# belamini-multi-a2.net
KiCad netlist of a schematic drawn in EAGLE
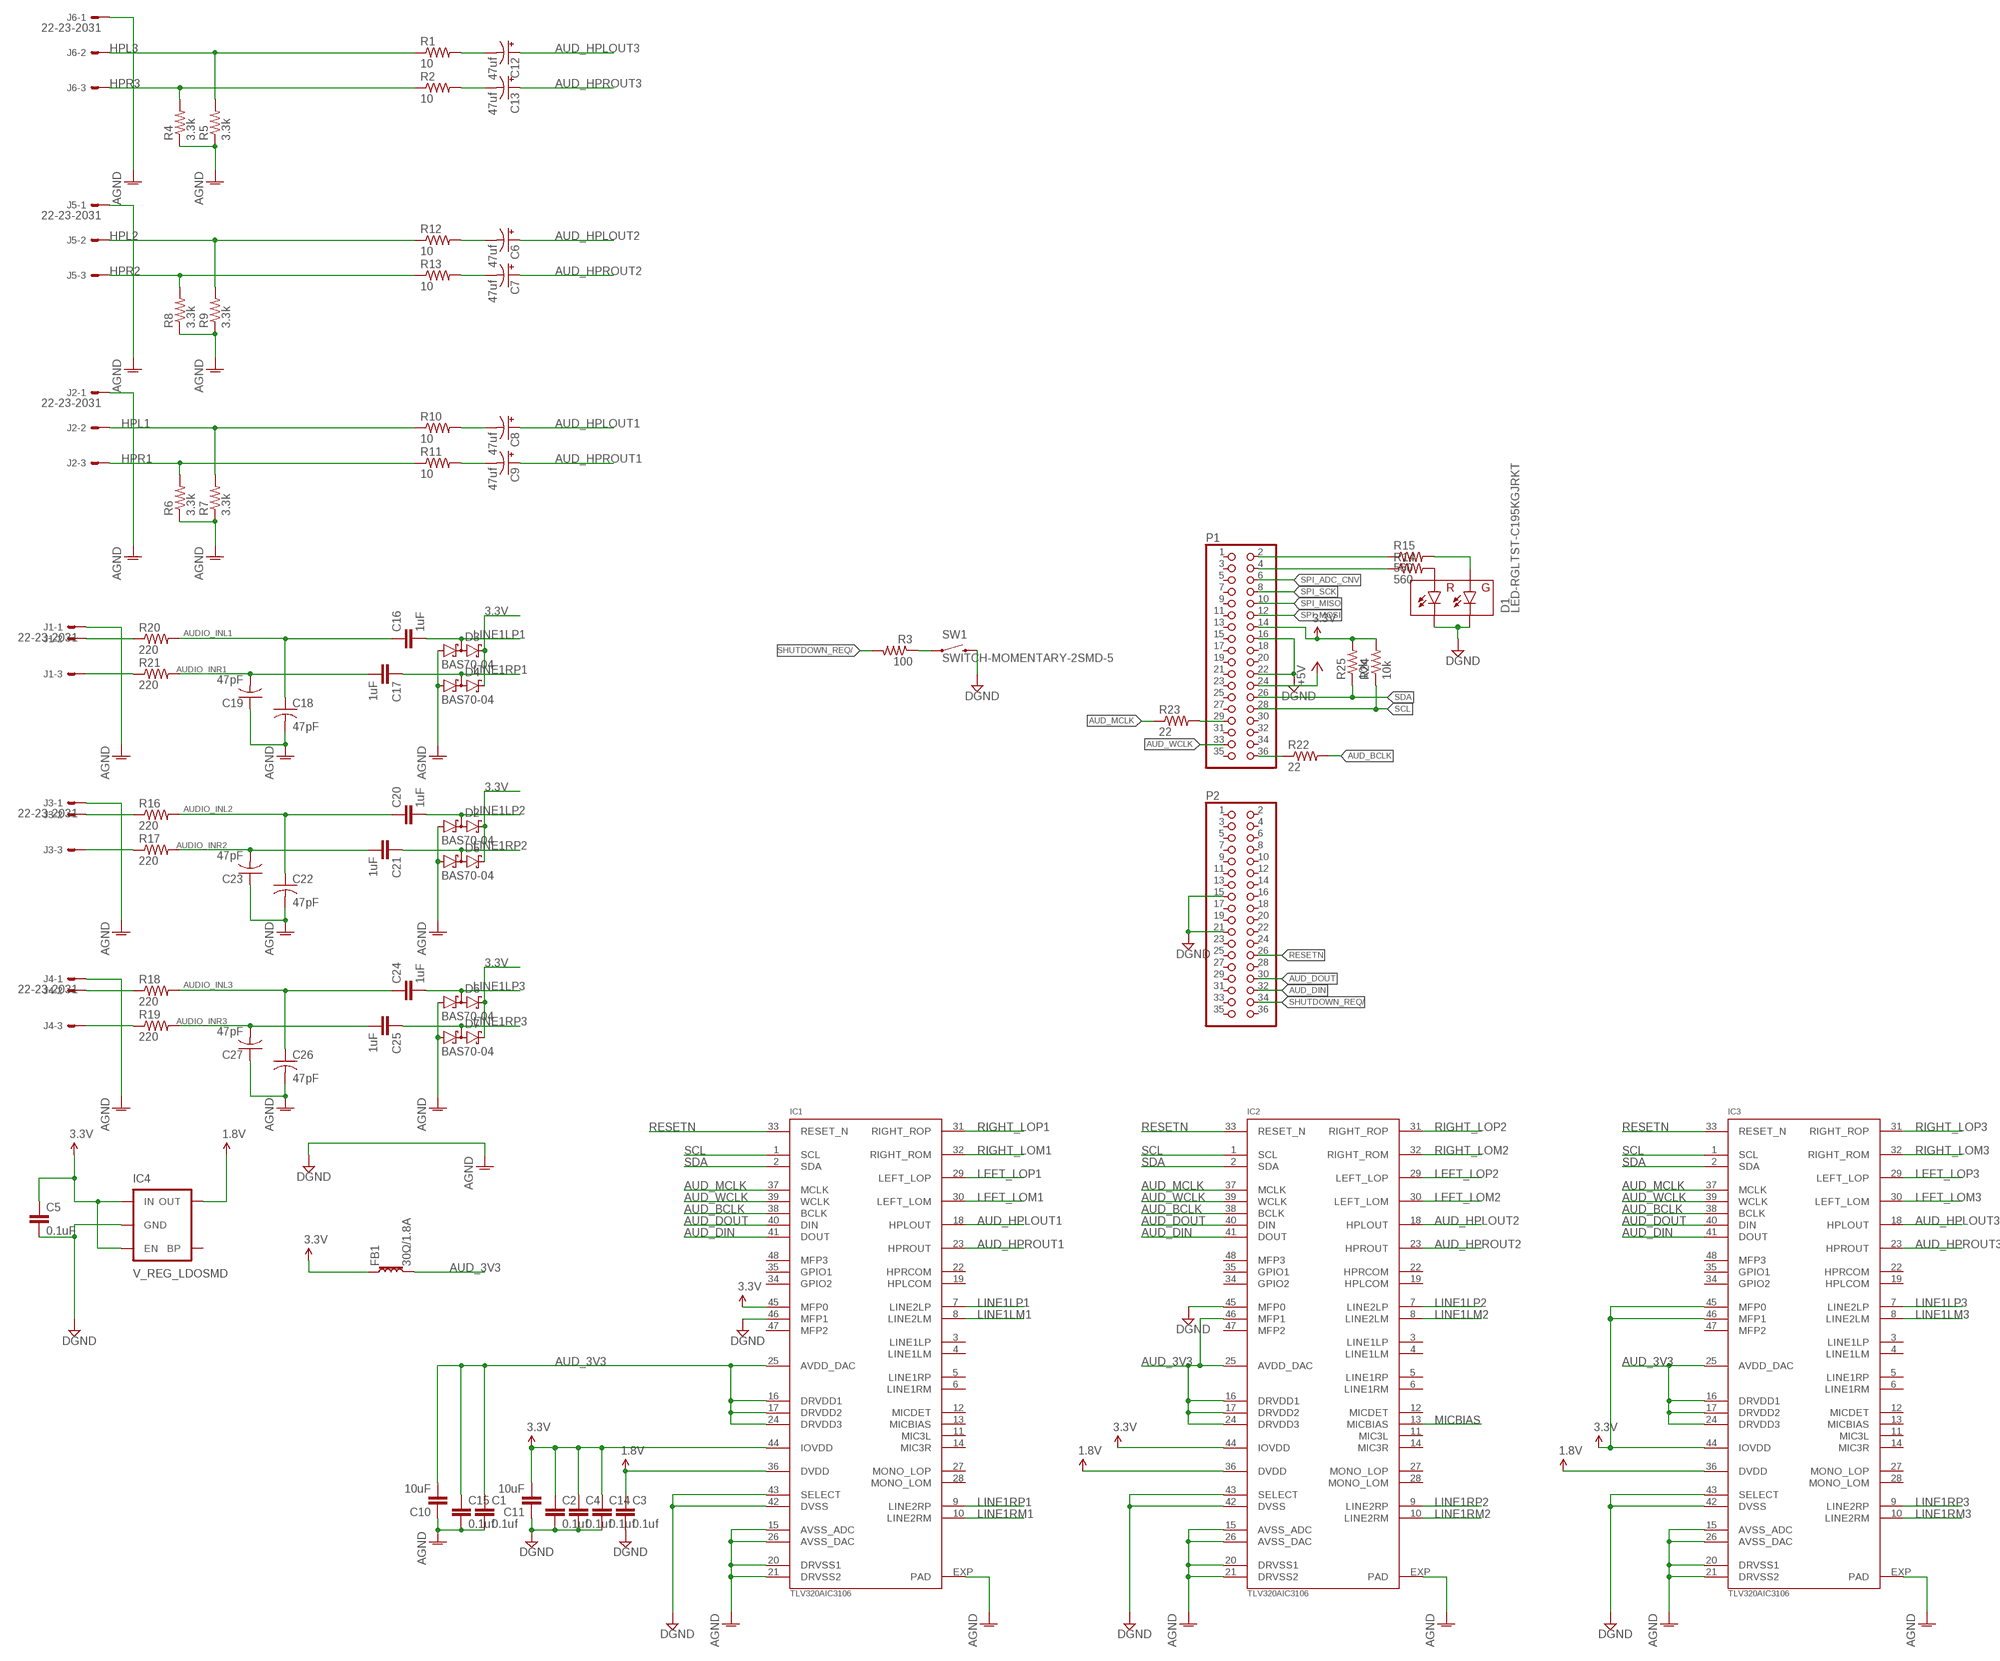
[diagram p0: schematic, sheet 1]

(export (version "E")
  (design (tool "Eeschema 10.0.6"))
  (components
    (comp (ref "C1")
      (value "0.1uf")
      (footprint "eagle-import:C0603")
      (libsource (lib "eagle-import") (part "C-EUC0603"))
    )
    (comp (ref "C2")
      (value "0.1uf")
      (footprint "eagle-import:C0603")
      (libsource (lib "eagle-import") (part "C-EUC0603"))
    )
    (comp (ref "C3")
      (value "0.1uf")
      (footprint "eagle-import:C0603")
      (libsource (lib "eagle-import") (part "C-EUC0603"))
    )
    (comp (ref "C4")
      (value "0.1uf")
      (footprint "eagle-import:C0603")
      (libsource (lib "eagle-import") (part "C-EUC0603"))
    )
    (comp (ref "C5")
      (value "0.1uF")
      (footprint "eagle-import:C0603")
      (libsource (lib "eagle-import") (part "C-EUC0603"))
    )
    (comp (ref "C6")
      (value "47uf")
      (footprint "eagle-import:EIA3216")
      (libsource (lib "eagle-import") (part "CAP_POL1206"))
    )
    (comp (ref "C7")
      (value "47uf")
      (footprint "eagle-import:EIA3216")
      (libsource (lib "eagle-import") (part "CAP_POL1206"))
    )
    (comp (ref "C8")
      (value "47uf")
      (footprint "eagle-import:EIA3216")
      (libsource (lib "eagle-import") (part "CAP_POL1206"))
    )
    (comp (ref "C9")
      (value "47uf")
      (footprint "eagle-import:EIA3216")
      (libsource (lib "eagle-import") (part "CAP_POL1206"))
    )
    (comp (ref "C10")
      (value "10uF")
      (footprint "eagle-import:0603-CAP")
      (libsource (lib "eagle-import") (part "CAP0603-CAP"))
    )
    (comp (ref "C11")
      (value "10uF")
      (footprint "eagle-import:0603-CAP")
      (libsource (lib "eagle-import") (part "CAP0603-CAP"))
    )
    (comp (ref "C12")
      (value "47uf")
      (footprint "eagle-import:EIA3216")
      (libsource (lib "eagle-import") (part "CAP_POL1206"))
    )
    (comp (ref "C13")
      (value "47uf")
      (footprint "eagle-import:EIA3216")
      (libsource (lib "eagle-import") (part "CAP_POL1206"))
    )
    (comp (ref "C14")
      (value "0.1uf")
      (footprint "eagle-import:C0603")
      (libsource (lib "eagle-import") (part "C-EUC0603"))
    )
    (comp (ref "C15")
      (value "0.1uf")
      (footprint "eagle-import:C0603")
      (libsource (lib "eagle-import") (part "C-EUC0603"))
    )
    (comp (ref "C16")
      (value "1uF")
      (footprint "eagle-import:C0603")
      (libsource (lib "eagle-import") (part "C-EUC0603"))
    )
    (comp (ref "C17")
      (value "1uF")
      (footprint "eagle-import:C0603")
      (libsource (lib "eagle-import") (part "C-EUC0603"))
    )
    (comp (ref "C18")
      (value "47pF")
      (footprint "eagle-import:C0402-SMALL")
      (libsource (lib "eagle-import") (part "C0402-SMALL"))
    )
    (comp (ref "C19")
      (value "47pF")
      (footprint "eagle-import:C0402-SMALL")
      (libsource (lib "eagle-import") (part "C0402-SMALL"))
    )
    (comp (ref "C20")
      (value "1uF")
      (footprint "eagle-import:C0603")
      (libsource (lib "eagle-import") (part "C-EUC0603"))
    )
    (comp (ref "C21")
      (value "1uF")
      (footprint "eagle-import:C0603")
      (libsource (lib "eagle-import") (part "C-EUC0603"))
    )
    (comp (ref "C22")
      (value "47pF")
      (footprint "eagle-import:C0402-SMALL")
      (libsource (lib "eagle-import") (part "C0402-SMALL"))
    )
    (comp (ref "C23")
      (value "47pF")
      (footprint "eagle-import:C0402-SMALL")
      (libsource (lib "eagle-import") (part "C0402-SMALL"))
    )
    (comp (ref "C24")
      (value "1uF")
      (footprint "eagle-import:C0603")
      (libsource (lib "eagle-import") (part "C-EUC0603"))
    )
    (comp (ref "C25")
      (value "1uF")
      (footprint "eagle-import:C0603")
      (libsource (lib "eagle-import") (part "C-EUC0603"))
    )
    (comp (ref "C26")
      (value "47pF")
      (footprint "eagle-import:C0402-SMALL")
      (libsource (lib "eagle-import") (part "C0402-SMALL"))
    )
    (comp (ref "C27")
      (value "47pF")
      (footprint "eagle-import:C0402-SMALL")
      (libsource (lib "eagle-import") (part "C0402-SMALL"))
    )
    (comp (ref "D1")
      (value "LED-RGLTST-C195KGJRKT")
      (footprint "eagle-import:LTST-C195KGJRKT")
      (libsource (lib "eagle-import") (part "LED-RGLTST-C195KGJRKT"))
    )
    (comp (ref "D2")
      (value "BAS70-04")
      (footprint "eagle-import:SOT23")
      (libsource (lib "eagle-import") (part "BAS70-04"))
    )
    (comp (ref "D3")
      (value "BAS70-04")
      (footprint "eagle-import:SOT23")
      (libsource (lib "eagle-import") (part "BAS70-04"))
    )
    (comp (ref "D4")
      (value "BAS70-04")
      (footprint "eagle-import:SOT23")
      (libsource (lib "eagle-import") (part "BAS70-04"))
    )
    (comp (ref "D5")
      (value "BAS70-04")
      (footprint "eagle-import:SOT23")
      (libsource (lib "eagle-import") (part "BAS70-04"))
    )
    (comp (ref "D6")
      (value "BAS70-04")
      (footprint "eagle-import:SOT23")
      (libsource (lib "eagle-import") (part "BAS70-04"))
    )
    (comp (ref "D7")
      (value "BAS70-04")
      (footprint "eagle-import:SOT23")
      (libsource (lib "eagle-import") (part "BAS70-04"))
    )
    (comp (ref "FB1")
      (value "30Ω/1.8A")
      (footprint "eagle-import:0603")
      (libsource (lib "eagle-import") (part "FERRITE_BEAD-0603"))
    )
    (comp (ref "IC1")
      (value "TLV320AIC3106")
      (footprint "eagle-import:QFN48")
      (libsource (lib "eagle-import") (part "TLV320AIC3106IRGZR{dblquote}"))
    )
    (comp (ref "IC2")
      (value "TLV320AIC3106")
      (footprint "eagle-import:QFN48")
      (libsource (lib "eagle-import") (part "TLV320AIC3106IRGZR{dblquote}"))
    )
    (comp (ref "IC3")
      (value "TLV320AIC3106")
      (footprint "eagle-import:QFN48")
      (libsource (lib "eagle-import") (part "TLV320AIC3106IRGZR{dblquote}"))
    )
    (comp (ref "IC4")
      (value "V_REG_LDOSMD")
      (footprint "eagle-import:SOT23-5")
      (libsource (lib "eagle-import") (part "V_REG_LDOSMD"))
    )
    (comp (ref "J1")
      (value "22-23-2031")
      (footprint "eagle-import:22-23-2031")
      (fields (field (name "MF") "MOLEX"))
      (libsource (lib "eagle-import") (part "22-23-2031"))
    )
    (comp (ref "J2")
      (value "22-23-2031")
      (footprint "eagle-import:22-23-2031")
      (fields (field (name "MF") "MOLEX"))
      (libsource (lib "eagle-import") (part "con-molex_165_22-23-2031"))
    )
    (comp (ref "J3")
      (value "22-23-2031")
      (footprint "eagle-import:22-23-2031")
      (fields (field (name "MF") "MOLEX"))
      (libsource (lib "eagle-import") (part "22-23-2031"))
    )
    (comp (ref "J4")
      (value "22-23-2031")
      (footprint "eagle-import:22-23-2031")
      (fields (field (name "MF") "MOLEX"))
      (libsource (lib "eagle-import") (part "22-23-2031"))
    )
    (comp (ref "J5")
      (value "22-23-2031")
      (footprint "eagle-import:22-23-2031")
      (fields (field (name "MF") "MOLEX"))
      (libsource (lib "eagle-import") (part "con-molex_165_22-23-2031"))
    )
    (comp (ref "J6")
      (value "22-23-2031")
      (footprint "eagle-import:22-23-2031")
      (fields (field (name "MF") "MOLEX"))
      (libsource (lib "eagle-import") (part "con-molex_165_22-23-2031"))
    )
    (comp (ref "P1")
      (value "PINHD-2X18")
      (footprint "eagle-import:2X18")
      (libsource (lib "eagle-import") (part "PINHD-2X18"))
    )
    (comp (ref "P2")
      (value "PINHD-2X18")
      (footprint "eagle-import:2X18")
      (libsource (lib "eagle-import") (part "PINHD-2X18"))
    )
    (comp (ref "R1")
      (value "10")
      (footprint "eagle-import:C0402-SMALL")
      (libsource (lib "eagle-import") (part "R0402-SMALL"))
    )
    (comp (ref "R2")
      (value "10")
      (footprint "eagle-import:C0402-SMALL")
      (libsource (lib "eagle-import") (part "R0402-SMALL"))
    )
    (comp (ref "R3")
      (value "100")
      (footprint "eagle-import:C0402-SMALL")
      (libsource (lib "eagle-import") (part "R0402-SMALL"))
    )
    (comp (ref "R4")
      (value "3.3k")
      (footprint "eagle-import:C0402-SMALL")
      (libsource (lib "eagle-import") (part "R0402-SMALL"))
    )
    (comp (ref "R5")
      (value "3.3k")
      (footprint "eagle-import:C0402-SMALL")
      (libsource (lib "eagle-import") (part "R0402-SMALL"))
    )
    (comp (ref "R6")
      (value "3.3k")
      (footprint "eagle-import:C0402-SMALL")
      (libsource (lib "eagle-import") (part "R0402-SMALL"))
    )
    (comp (ref "R7")
      (value "3.3k")
      (footprint "eagle-import:C0402-SMALL")
      (libsource (lib "eagle-import") (part "R0402-SMALL"))
    )
    (comp (ref "R8")
      (value "3.3k")
      (footprint "eagle-import:C0402-SMALL")
      (libsource (lib "eagle-import") (part "R0402-SMALL"))
    )
    (comp (ref "R9")
      (value "3.3k")
      (footprint "eagle-import:C0402-SMALL")
      (libsource (lib "eagle-import") (part "R0402-SMALL"))
    )
    (comp (ref "R10")
      (value "10")
      (footprint "eagle-import:C0402-SMALL")
      (libsource (lib "eagle-import") (part "R0402-SMALL"))
    )
    (comp (ref "R11")
      (value "10")
      (footprint "eagle-import:C0402-SMALL")
      (libsource (lib "eagle-import") (part "R0402-SMALL"))
    )
    (comp (ref "R12")
      (value "10")
      (footprint "eagle-import:C0402-SMALL")
      (libsource (lib "eagle-import") (part "R0402-SMALL"))
    )
    (comp (ref "R13")
      (value "10")
      (footprint "eagle-import:C0402-SMALL")
      (libsource (lib "eagle-import") (part "R0402-SMALL"))
    )
    (comp (ref "R14")
      (value "560")
      (footprint "eagle-import:C0402-SMALL")
      (libsource (lib "eagle-import") (part "R0402-SMALL"))
    )
    (comp (ref "R15")
      (value "560")
      (footprint "eagle-import:C0402-SMALL")
      (libsource (lib "eagle-import") (part "R0402-SMALL"))
    )
    (comp (ref "R16")
      (value "220")
      (footprint "eagle-import:C0402-SMALL")
      (libsource (lib "eagle-import") (part "R0402-SMALL"))
    )
    (comp (ref "R17")
      (value "220")
      (footprint "eagle-import:C0402-SMALL")
      (libsource (lib "eagle-import") (part "R0402-SMALL"))
    )
    (comp (ref "R18")
      (value "220")
      (footprint "eagle-import:C0402-SMALL")
      (libsource (lib "eagle-import") (part "R0402-SMALL"))
    )
    (comp (ref "R19")
      (value "220")
      (footprint "eagle-import:C0402-SMALL")
      (libsource (lib "eagle-import") (part "R0402-SMALL"))
    )
    (comp (ref "R20")
      (value "220")
      (footprint "eagle-import:C0402-SMALL")
      (libsource (lib "eagle-import") (part "R0402-SMALL"))
    )
    (comp (ref "R21")
      (value "220")
      (footprint "eagle-import:C0402-SMALL")
      (libsource (lib "eagle-import") (part "R0402-SMALL"))
    )
    (comp (ref "R22")
      (value "22")
      (footprint "eagle-import:C0402-SMALL")
      (libsource (lib "eagle-import") (part "R0402-SMALL"))
    )
    (comp (ref "R23")
      (value "22")
      (footprint "eagle-import:C0402-SMALL")
      (libsource (lib "eagle-import") (part "R0402-SMALL"))
    )
    (comp (ref "R24")
      (value "10k")
      (footprint "eagle-import:C0402-SMALL")
      (libsource (lib "eagle-import") (part "R0402-SMALL"))
    )
    (comp (ref "R25")
      (value "10k")
      (footprint "eagle-import:C0402-SMALL")
      (libsource (lib "eagle-import") (part "R0402-SMALL"))
    )
    (comp (ref "SW1")
      (value "SWITCH-MOMENTARY-2SMD-5")
      (footprint "eagle-import:TACTILE_SWITCH_SMD-4")
      (libsource (lib "eagle-import") (part "SWITCH-MOMENTARY-2SMD-5"))
    )
  )
  (nets
    (net (code "1") (name "+5V") (class "Default")
      (node (ref "P1") (pin "24") (pinfunction "24_24") (pintype "passive"))
    )
    (net (code "2") (name "/AUDIO_INL1") (class "Default")
      (node (ref "C16") (pin "1") (pinfunction "1_1") (pintype "passive"))
      (node (ref "C18") (pin "P$1") (pinfunction "1_P$1") (pintype "passive"))
      (node (ref "R20") (pin "P$2") (pinfunction "2_P$2") (pintype "passive"))
    )
    (net (code "3") (name "/AUDIO_INL2") (class "Default")
      (node (ref "C20") (pin "1") (pinfunction "1_1") (pintype "passive"))
      (node (ref "C22") (pin "P$1") (pinfunction "1_P$1") (pintype "passive"))
      (node (ref "R16") (pin "P$2") (pinfunction "2_P$2") (pintype "passive"))
    )
    (net (code "4") (name "/AUDIO_INL3") (class "Default")
      (node (ref "C24") (pin "1") (pinfunction "1_1") (pintype "passive"))
      (node (ref "C26") (pin "P$1") (pinfunction "1_P$1") (pintype "passive"))
      (node (ref "R18") (pin "P$2") (pinfunction "2_P$2") (pintype "passive"))
    )
    (net (code "5") (name "/AUDIO_INR1") (class "Default")
      (node (ref "C17") (pin "2") (pinfunction "2_2") (pintype "passive"))
      (node (ref "C19") (pin "P$2") (pinfunction "2_P$2") (pintype "passive"))
      (node (ref "R21") (pin "P$2") (pinfunction "2_P$2") (pintype "passive"))
    )
    (net (code "6") (name "/AUDIO_INR2") (class "Default")
      (node (ref "C21") (pin "2") (pinfunction "2_2") (pintype "passive"))
      (node (ref "C23") (pin "P$2") (pinfunction "2_P$2") (pintype "passive"))
      (node (ref "R17") (pin "P$2") (pinfunction "2_P$2") (pintype "passive"))
    )
    (net (code "7") (name "/AUDIO_INR3") (class "Default")
      (node (ref "C25") (pin "2") (pinfunction "2_2") (pintype "passive"))
      (node (ref "C27") (pin "P$2") (pinfunction "2_P$2") (pintype "passive"))
      (node (ref "R19") (pin "P$2") (pinfunction "2_P$2") (pintype "passive"))
    )
    (net (code "8") (name "/AUD_3V3") (class "Default")
      (node (ref "C1") (pin "1") (pinfunction "1_1") (pintype "passive"))
      (node (ref "C10") (pin "2") (pinfunction "2_2") (pintype "passive"))
      (node (ref "C15") (pin "1") (pinfunction "1_1") (pintype "passive"))
      (node (ref "FB1") (pin "2") (pinfunction "2_2") (pintype "passive"))
      (node (ref "IC1") (pin "16") (pinfunction "DRVDD1_16") (pintype "bidirectional"))
      (node (ref "IC1") (pin "17") (pinfunction "DRVDD2_17") (pintype "bidirectional"))
      (node (ref "IC1") (pin "24") (pinfunction "DRVDD3_24") (pintype "bidirectional"))
      (node (ref "IC1") (pin "25") (pinfunction "AVDD_DAC_25") (pintype "bidirectional"))
      (node (ref "IC2") (pin "16") (pinfunction "DRVDD1_16") (pintype "bidirectional"))
      (node (ref "IC2") (pin "17") (pinfunction "DRVDD2_17") (pintype "bidirectional"))
      (node (ref "IC2") (pin "24") (pinfunction "DRVDD3_24") (pintype "bidirectional"))
      (node (ref "IC2") (pin "25") (pinfunction "AVDD_DAC_25") (pintype "bidirectional"))
      (node (ref "IC2") (pin "46") (pinfunction "MFP1_46") (pintype "bidirectional"))
      (node (ref "IC3") (pin "16") (pinfunction "DRVDD1_16") (pintype "bidirectional"))
      (node (ref "IC3") (pin "17") (pinfunction "DRVDD2_17") (pintype "bidirectional"))
      (node (ref "IC3") (pin "24") (pinfunction "DRVDD3_24") (pintype "bidirectional"))
      (node (ref "IC3") (pin "25") (pinfunction "AVDD_DAC_25") (pintype "bidirectional"))
    )
    (net (code "9") (name "/AUD_HPLOUT1") (class "Default")
      (node (ref "C8") (pin "A") (pinfunction "+_A") (pintype "passive"))
      (node (ref "IC1") (pin "18") (pinfunction "HPLOUT_18") (pintype "bidirectional"))
    )
    (net (code "10") (name "/AUD_HPLOUT2") (class "Default")
      (node (ref "C6") (pin "A") (pinfunction "+_A") (pintype "passive"))
      (node (ref "IC2") (pin "18") (pinfunction "HPLOUT_18") (pintype "bidirectional"))
    )
    (net (code "11") (name "/AUD_HPLOUT3") (class "Default")
      (node (ref "C12") (pin "A") (pinfunction "+_A") (pintype "passive"))
      (node (ref "IC3") (pin "18") (pinfunction "HPLOUT_18") (pintype "bidirectional"))
    )
    (net (code "12") (name "/AUD_HPROUT1") (class "Default")
      (node (ref "C9") (pin "A") (pinfunction "+_A") (pintype "passive"))
      (node (ref "IC1") (pin "23") (pinfunction "HPROUT_23") (pintype "bidirectional"))
    )
    (net (code "13") (name "/AUD_HPROUT2") (class "Default")
      (node (ref "C7") (pin "A") (pinfunction "+_A") (pintype "passive"))
      (node (ref "IC2") (pin "23") (pinfunction "HPROUT_23") (pintype "bidirectional"))
    )
    (net (code "14") (name "/AUD_HPROUT3") (class "Default")
      (node (ref "C13") (pin "A") (pinfunction "+_A") (pintype "passive"))
      (node (ref "IC3") (pin "23") (pinfunction "HPROUT_23") (pintype "bidirectional"))
    )
    (net (code "15") (name "/HPL1") (class "Default")
      (node (ref "J2") (pin "2") (pinfunction "S_2") (pintype "passive"))
      (node (ref "R10") (pin "P$1") (pinfunction "1_P$1") (pintype "passive"))
      (node (ref "R7") (pin "P$2") (pinfunction "2_P$2") (pintype "passive"))
    )
    (net (code "16") (name "/HPL2") (class "Default")
      (node (ref "J5") (pin "2") (pinfunction "S_2") (pintype "passive"))
      (node (ref "R12") (pin "P$1") (pinfunction "1_P$1") (pintype "passive"))
      (node (ref "R9") (pin "P$2") (pinfunction "2_P$2") (pintype "passive"))
    )
    (net (code "17") (name "/HPL3") (class "Default")
      (node (ref "J6") (pin "2") (pinfunction "S_2") (pintype "passive"))
      (node (ref "R1") (pin "P$1") (pinfunction "1_P$1") (pintype "passive"))
      (node (ref "R5") (pin "P$2") (pinfunction "2_P$2") (pintype "passive"))
    )
    (net (code "18") (name "/HPR1") (class "Default")
      (node (ref "J2") (pin "3") (pinfunction "S_3") (pintype "passive"))
      (node (ref "R11") (pin "P$1") (pinfunction "1_P$1") (pintype "passive"))
      (node (ref "R6") (pin "P$2") (pinfunction "2_P$2") (pintype "passive"))
    )
    (net (code "19") (name "/HPR2") (class "Default")
      (node (ref "J5") (pin "3") (pinfunction "S_3") (pintype "passive"))
      (node (ref "R13") (pin "P$1") (pinfunction "1_P$1") (pintype "passive"))
      (node (ref "R8") (pin "P$2") (pinfunction "2_P$2") (pintype "passive"))
    )
    (net (code "20") (name "/HPR3") (class "Default")
      (node (ref "J6") (pin "3") (pinfunction "S_3") (pintype "passive"))
      (node (ref "R2") (pin "P$1") (pinfunction "1_P$1") (pintype "passive"))
      (node (ref "R4") (pin "P$2") (pinfunction "2_P$2") (pintype "passive"))
    )
    (net (code "21") (name "/LEFT_LOM1") (class "Default")
      (node (ref "IC1") (pin "30") (pinfunction "LEFT_LOM_30") (pintype "bidirectional"))
    )
    (net (code "22") (name "/LEFT_LOM2") (class "Default")
      (node (ref "IC2") (pin "30") (pinfunction "LEFT_LOM_30") (pintype "bidirectional"))
    )
    (net (code "23") (name "/LEFT_LOM3") (class "Default")
      (node (ref "IC3") (pin "30") (pinfunction "LEFT_LOM_30") (pintype "bidirectional"))
    )
    (net (code "24") (name "/LEFT_LOP1") (class "Default")
      (node (ref "IC1") (pin "29") (pinfunction "LEFT_LOP_29") (pintype "bidirectional"))
    )
    (net (code "25") (name "/LEFT_LOP2") (class "Default")
      (node (ref "IC2") (pin "29") (pinfunction "LEFT_LOP_29") (pintype "bidirectional"))
    )
    (net (code "26") (name "/LEFT_LOP3") (class "Default")
      (node (ref "IC3") (pin "29") (pinfunction "LEFT_LOP_29") (pintype "bidirectional"))
    )
    (net (code "27") (name "/LINE1LM1") (class "Default")
      (node (ref "IC1") (pin "8") (pinfunction "LINE2LM_8") (pintype "bidirectional"))
    )
    (net (code "28") (name "/LINE1LM2") (class "Default")
      (node (ref "IC2") (pin "8") (pinfunction "LINE2LM_8") (pintype "bidirectional"))
    )
    (net (code "29") (name "/LINE1LM3") (class "Default")
      (node (ref "IC3") (pin "8") (pinfunction "LINE2LM_8") (pintype "bidirectional"))
    )
    (net (code "30") (name "/LINE1LP1") (class "Default")
      (node (ref "C16") (pin "2") (pinfunction "2_2") (pintype "passive"))
      (node (ref "D3") (pin "3") (pinfunction "C1A2_3") (pintype "passive"))
      (node (ref "IC1") (pin "7") (pinfunction "LINE2LP_7") (pintype "bidirectional"))
    )
    (net (code "31") (name "/LINE1LP2") (class "Default")
      (node (ref "C20") (pin "2") (pinfunction "2_2") (pintype "passive"))
      (node (ref "D2") (pin "3") (pinfunction "C1A2_3") (pintype "passive"))
      (node (ref "IC2") (pin "7") (pinfunction "LINE2LP_7") (pintype "bidirectional"))
    )
    (net (code "32") (name "/LINE1LP3") (class "Default")
      (node (ref "C24") (pin "2") (pinfunction "2_2") (pintype "passive"))
      (node (ref "D6") (pin "3") (pinfunction "C1A2_3") (pintype "passive"))
      (node (ref "IC3") (pin "7") (pinfunction "LINE2LP_7") (pintype "bidirectional"))
    )
    (net (code "33") (name "/LINE1RM1") (class "Default")
      (node (ref "IC1") (pin "10") (pinfunction "LINE2RM_10") (pintype "bidirectional"))
    )
    (net (code "34") (name "/LINE1RM2") (class "Default")
      (node (ref "IC2") (pin "10") (pinfunction "LINE2RM_10") (pintype "bidirectional"))
    )
    (net (code "35") (name "/LINE1RM3") (class "Default")
      (node (ref "IC3") (pin "10") (pinfunction "LINE2RM_10") (pintype "bidirectional"))
    )
    (net (code "36") (name "/LINE1RP1") (class "Default")
      (node (ref "C17") (pin "1") (pinfunction "1_1") (pintype "passive"))
      (node (ref "D4") (pin "3") (pinfunction "C1A2_3") (pintype "passive"))
      (node (ref "IC1") (pin "9") (pinfunction "LINE2RP_9") (pintype "bidirectional"))
    )
    (net (code "37") (name "/LINE1RP2") (class "Default")
      (node (ref "C21") (pin "1") (pinfunction "1_1") (pintype "passive"))
      (node (ref "D5") (pin "3") (pinfunction "C1A2_3") (pintype "passive"))
      (node (ref "IC2") (pin "9") (pinfunction "LINE2RP_9") (pintype "bidirectional"))
    )
    (net (code "38") (name "/LINE1RP3") (class "Default")
      (node (ref "C25") (pin "1") (pinfunction "1_1") (pintype "passive"))
      (node (ref "D7") (pin "3") (pinfunction "C1A2_3") (pintype "passive"))
      (node (ref "IC3") (pin "9") (pinfunction "LINE2RP_9") (pintype "bidirectional"))
    )
    (net (code "39") (name "/MICBIAS") (class "Default")
      (node (ref "IC2") (pin "13") (pinfunction "MICBIAS_13") (pintype "bidirectional"))
    )
    (net (code "40") (name "/RIGHT_LOM1") (class "Default")
      (node (ref "IC1") (pin "32") (pinfunction "RIGHT_ROM_32") (pintype "bidirectional"))
    )
    (net (code "41") (name "/RIGHT_LOM2") (class "Default")
      (node (ref "IC2") (pin "32") (pinfunction "RIGHT_ROM_32") (pintype "bidirectional"))
    )
    (net (code "42") (name "/RIGHT_LOM3") (class "Default")
      (node (ref "IC3") (pin "32") (pinfunction "RIGHT_ROM_32") (pintype "bidirectional"))
    )
    (net (code "43") (name "/RIGHT_LOP1") (class "Default")
      (node (ref "IC1") (pin "31") (pinfunction "RIGHT_ROP_31") (pintype "bidirectional"))
    )
    (net (code "44") (name "/RIGHT_LOP2") (class "Default")
      (node (ref "IC2") (pin "31") (pinfunction "RIGHT_ROP_31") (pintype "bidirectional"))
    )
    (net (code "45") (name "/RIGHT_LOP3") (class "Default")
      (node (ref "IC3") (pin "31") (pinfunction "RIGHT_ROP_31") (pintype "bidirectional"))
    )
    (net (code "46") (name "1.8V") (class "Default")
      (node (ref "C3") (pin "1") (pinfunction "1_1") (pintype "passive"))
      (node (ref "IC1") (pin "36") (pinfunction "DVDD_36") (pintype "bidirectional"))
      (node (ref "IC2") (pin "36") (pinfunction "DVDD_36") (pintype "bidirectional"))
      (node (ref "IC3") (pin "36") (pinfunction "DVDD_36") (pintype "bidirectional"))
      (node (ref "IC4") (pin "5") (pinfunction "OUT_5") (pintype "passive"))
    )
    (net (code "47") (name "3.3V") (class "Default")
      (node (ref "C11") (pin "2") (pinfunction "2_2") (pintype "passive"))
      (node (ref "C14") (pin "1") (pinfunction "1_1") (pintype "passive"))
      (node (ref "C2") (pin "1") (pinfunction "1_1") (pintype "passive"))
      (node (ref "C4") (pin "1") (pinfunction "1_1") (pintype "passive"))
      (node (ref "C5") (pin "1") (pinfunction "1_1") (pintype "passive"))
      (node (ref "D2") (pin "2") (pinfunction "C2_2") (pintype "passive"))
      (node (ref "D3") (pin "2") (pinfunction "C2_2") (pintype "passive"))
      (node (ref "D4") (pin "2") (pinfunction "C2_2") (pintype "passive"))
      (node (ref "D5") (pin "2") (pinfunction "C2_2") (pintype "passive"))
      (node (ref "D6") (pin "2") (pinfunction "C2_2") (pintype "passive"))
      (node (ref "D7") (pin "2") (pinfunction "C2_2") (pintype "passive"))
      (node (ref "FB1") (pin "1") (pinfunction "1_1") (pintype "passive"))
      (node (ref "IC1") (pin "44") (pinfunction "IOVDD_44") (pintype "bidirectional"))
      (node (ref "IC1") (pin "45") (pinfunction "MFP0_45") (pintype "bidirectional"))
      (node (ref "IC2") (pin "44") (pinfunction "IOVDD_44") (pintype "bidirectional"))
      (node (ref "IC3") (pin "44") (pinfunction "IOVDD_44") (pintype "bidirectional"))
      (node (ref "IC3") (pin "45") (pinfunction "MFP0_45") (pintype "bidirectional"))
      (node (ref "IC3") (pin "46") (pinfunction "MFP1_46") (pintype "bidirectional"))
      (node (ref "IC4") (pin "1") (pinfunction "IN_1") (pintype "input"))
      (node (ref "IC4") (pin "3") (pinfunction "EN_3") (pintype "input"))
      (node (ref "P1") (pin "14") (pinfunction "14_14") (pintype "passive"))
      (node (ref "R24") (pin "P$2") (pinfunction "2_P$2") (pintype "passive"))
      (node (ref "R25") (pin "P$2") (pinfunction "2_P$2") (pintype "passive"))
    )
    (net (code "48") (name "AGND") (class "Default")
      (node (ref "C1") (pin "2") (pinfunction "2_2") (pintype "passive"))
      (node (ref "C10") (pin "1") (pinfunction "1_1") (pintype "passive"))
      (node (ref "C11") (pin "1") (pinfunction "1_1") (pintype "passive"))
      (node (ref "C14") (pin "2") (pinfunction "2_2") (pintype "passive"))
      (node (ref "C15") (pin "2") (pinfunction "2_2") (pintype "passive"))
      (node (ref "C18") (pin "P$2") (pinfunction "2_P$2") (pintype "passive"))
      (node (ref "C19") (pin "P$1") (pinfunction "1_P$1") (pintype "passive"))
      (node (ref "C2") (pin "2") (pinfunction "2_2") (pintype "passive"))
      (node (ref "C22") (pin "P$2") (pinfunction "2_P$2") (pintype "passive"))
      (node (ref "C23") (pin "P$1") (pinfunction "1_P$1") (pintype "passive"))
      (node (ref "C26") (pin "P$2") (pinfunction "2_P$2") (pintype "passive"))
      (node (ref "C27") (pin "P$1") (pinfunction "1_P$1") (pintype "passive"))
      (node (ref "C3") (pin "2") (pinfunction "2_2") (pintype "passive"))
      (node (ref "C4") (pin "2") (pinfunction "2_2") (pintype "passive"))
      (node (ref "C5") (pin "2") (pinfunction "2_2") (pintype "passive"))
      (node (ref "D1") (pin "P$3") (pinfunction "GC_P$3") (pintype "passive"))
      (node (ref "D1") (pin "P$4") (pinfunction "RC_P$4") (pintype "passive"))
      (node (ref "D2") (pin "1") (pinfunction "A1_1") (pintype "passive"))
      (node (ref "D3") (pin "1") (pinfunction "A1_1") (pintype "passive"))
      (node (ref "D4") (pin "1") (pinfunction "A1_1") (pintype "passive"))
      (node (ref "D5") (pin "1") (pinfunction "A1_1") (pintype "passive"))
      (node (ref "D6") (pin "1") (pinfunction "A1_1") (pintype "passive"))
      (node (ref "D7") (pin "1") (pinfunction "A1_1") (pintype "passive"))
      (node (ref "IC1") (pin "15") (pinfunction "AVSS_ADC_15") (pintype "bidirectional"))
      (node (ref "IC1") (pin "20") (pinfunction "DRVSS1_20") (pintype "bidirectional"))
      (node (ref "IC1") (pin "21") (pinfunction "DRVSS2_21") (pintype "bidirectional"))
      (node (ref "IC1") (pin "26") (pinfunction "AVSS_DAC_26") (pintype "bidirectional"))
      (node (ref "IC1") (pin "42") (pinfunction "DVSS_42") (pintype "bidirectional"))
      (node (ref "IC1") (pin "43") (pinfunction "SELECT_43") (pintype "bidirectional"))
      (node (ref "IC1") (pin "46") (pinfunction "MFP1_46") (pintype "bidirectional"))
      (node (ref "IC1") (pin "EXP") (pinfunction "PAD_EXP") (pintype "bidirectional"))
      (node (ref "IC2") (pin "15") (pinfunction "AVSS_ADC_15") (pintype "bidirectional"))
      (node (ref "IC2") (pin "20") (pinfunction "DRVSS1_20") (pintype "bidirectional"))
      (node (ref "IC2") (pin "21") (pinfunction "DRVSS2_21") (pintype "bidirectional"))
      (node (ref "IC2") (pin "26") (pinfunction "AVSS_DAC_26") (pintype "bidirectional"))
      (node (ref "IC2") (pin "42") (pinfunction "DVSS_42") (pintype "bidirectional"))
      (node (ref "IC2") (pin "43") (pinfunction "SELECT_43") (pintype "bidirectional"))
      (node (ref "IC2") (pin "45") (pinfunction "MFP0_45") (pintype "bidirectional"))
      (node (ref "IC2") (pin "EXP") (pinfunction "PAD_EXP") (pintype "bidirectional"))
      (node (ref "IC3") (pin "15") (pinfunction "AVSS_ADC_15") (pintype "bidirectional"))
      (node (ref "IC3") (pin "20") (pinfunction "DRVSS1_20") (pintype "bidirectional"))
      (node (ref "IC3") (pin "21") (pinfunction "DRVSS2_21") (pintype "bidirectional"))
      (node (ref "IC3") (pin "26") (pinfunction "AVSS_DAC_26") (pintype "bidirectional"))
      (node (ref "IC3") (pin "42") (pinfunction "DVSS_42") (pintype "bidirectional"))
      (node (ref "IC3") (pin "43") (pinfunction "SELECT_43") (pintype "bidirectional"))
      (node (ref "IC3") (pin "EXP") (pinfunction "PAD_EXP") (pintype "bidirectional"))
      (node (ref "IC4") (pin "2") (pinfunction "GND_2") (pintype "input"))
      (node (ref "J1") (pin "1") (pinfunction "S_1") (pintype "passive"))
      (node (ref "J2") (pin "1") (pinfunction "S_1") (pintype "passive"))
      (node (ref "J3") (pin "1") (pinfunction "S_1") (pintype "passive"))
      (node (ref "J4") (pin "1") (pinfunction "S_1") (pintype "passive"))
      (node (ref "J5") (pin "1") (pinfunction "S_1") (pintype "passive"))
      (node (ref "J6") (pin "1") (pinfunction "S_1") (pintype "passive"))
      (node (ref "P1") (pin "16") (pinfunction "16_16") (pintype "passive"))
      (node (ref "P1") (pin "22") (pinfunction "22_22") (pintype "passive"))
      (node (ref "P2") (pin "15") (pinfunction "15_15") (pintype "passive"))
      (node (ref "P2") (pin "21") (pinfunction "21_21") (pintype "passive"))
      (node (ref "R4") (pin "P$1") (pinfunction "1_P$1") (pintype "passive"))
      (node (ref "R5") (pin "P$1") (pinfunction "1_P$1") (pintype "passive"))
      (node (ref "R6") (pin "P$1") (pinfunction "1_P$1") (pintype "passive"))
      (node (ref "R7") (pin "P$1") (pinfunction "1_P$1") (pintype "passive"))
      (node (ref "R8") (pin "P$1") (pinfunction "1_P$1") (pintype "passive"))
      (node (ref "R9") (pin "P$1") (pinfunction "1_P$1") (pintype "passive"))
      (node (ref "SW1") (pin "4") (pinfunction "2_4") (pintype "passive"))
    )
    (net (code "49") (name "AUD_BCLK") (class "Default")
      (node (ref "IC1") (pin "38") (pinfunction "BCLK_38") (pintype "bidirectional"))
      (node (ref "IC2") (pin "38") (pinfunction "BCLK_38") (pintype "bidirectional"))
      (node (ref "IC3") (pin "38") (pinfunction "BCLK_38") (pintype "bidirectional"))
      (node (ref "R22") (pin "P$2") (pinfunction "2_P$2") (pintype "passive"))
    )
    (net (code "50") (name "AUD_DIN") (class "Default")
      (node (ref "IC1") (pin "41") (pinfunction "DOUT_41") (pintype "bidirectional"))
      (node (ref "IC2") (pin "41") (pinfunction "DOUT_41") (pintype "bidirectional"))
      (node (ref "IC3") (pin "41") (pinfunction "DOUT_41") (pintype "bidirectional"))
      (node (ref "P2") (pin "32") (pinfunction "32_32") (pintype "passive"))
    )
    (net (code "51") (name "AUD_DOUT") (class "Default")
      (node (ref "IC1") (pin "40") (pinfunction "DIN_40") (pintype "bidirectional"))
      (node (ref "IC2") (pin "40") (pinfunction "DIN_40") (pintype "bidirectional"))
      (node (ref "IC3") (pin "40") (pinfunction "DIN_40") (pintype "bidirectional"))
      (node (ref "P2") (pin "30") (pinfunction "30_30") (pintype "passive"))
    )
    (net (code "52") (name "AUD_MCLK") (class "Default")
      (node (ref "IC1") (pin "37") (pinfunction "MCLK_37") (pintype "bidirectional"))
      (node (ref "IC2") (pin "37") (pinfunction "MCLK_37") (pintype "bidirectional"))
      (node (ref "IC3") (pin "37") (pinfunction "MCLK_37") (pintype "bidirectional"))
      (node (ref "R23") (pin "P$1") (pinfunction "1_P$1") (pintype "passive"))
    )
    (net (code "53") (name "AUD_WCLK") (class "Default")
      (node (ref "IC1") (pin "39") (pinfunction "WCLK_39") (pintype "bidirectional"))
      (node (ref "IC2") (pin "39") (pinfunction "WCLK_39") (pintype "bidirectional"))
      (node (ref "IC3") (pin "39") (pinfunction "WCLK_39") (pintype "bidirectional"))
      (node (ref "P1") (pin "33") (pinfunction "33_33") (pintype "passive"))
    )
    (net (code "54") (name "Net-(C6--)") (class "Default")
      (node (ref "C6") (pin "C") (pinfunction "-_C") (pintype "passive"))
      (node (ref "R12") (pin "P$2") (pinfunction "2_P$2") (pintype "passive"))
    )
    (net (code "55") (name "Net-(C7--)") (class "Default")
      (node (ref "C7") (pin "C") (pinfunction "-_C") (pintype "passive"))
      (node (ref "R13") (pin "P$2") (pinfunction "2_P$2") (pintype "passive"))
    )
    (net (code "56") (name "Net-(C8--)") (class "Default")
      (node (ref "C8") (pin "C") (pinfunction "-_C") (pintype "passive"))
      (node (ref "R10") (pin "P$2") (pinfunction "2_P$2") (pintype "passive"))
    )
    (net (code "57") (name "Net-(C9--)") (class "Default")
      (node (ref "C9") (pin "C") (pinfunction "-_C") (pintype "passive"))
      (node (ref "R11") (pin "P$2") (pinfunction "2_P$2") (pintype "passive"))
    )
    (net (code "58") (name "Net-(C12--)") (class "Default")
      (node (ref "C12") (pin "C") (pinfunction "-_C") (pintype "passive"))
      (node (ref "R1") (pin "P$2") (pinfunction "2_P$2") (pintype "passive"))
    )
    (net (code "59") (name "Net-(C13--)") (class "Default")
      (node (ref "C13") (pin "C") (pinfunction "-_C") (pintype "passive"))
      (node (ref "R2") (pin "P$2") (pinfunction "2_P$2") (pintype "passive"))
    )
    (net (code "60") (name "Net-(D1-GA)") (class "Default")
      (node (ref "D1") (pin "P$1") (pinfunction "GA_P$1") (pintype "passive"))
      (node (ref "R15") (pin "P$2") (pinfunction "2_P$2") (pintype "passive"))
    )
    (net (code "61") (name "Net-(D1-RA)") (class "Default")
      (node (ref "D1") (pin "P$2") (pinfunction "RA_P$2") (pintype "passive"))
      (node (ref "R14") (pin "P$2") (pinfunction "2_P$2") (pintype "passive"))
    )
    (net (code "62") (name "Net-(J1B-S)") (class "Default")
      (node (ref "J1") (pin "2") (pinfunction "S_2") (pintype "passive"))
      (node (ref "R20") (pin "P$1") (pinfunction "1_P$1") (pintype "passive"))
    )
    (net (code "63") (name "Net-(J1C-S)") (class "Default")
      (node (ref "J1") (pin "3") (pinfunction "S_3") (pintype "passive"))
      (node (ref "R21") (pin "P$1") (pinfunction "1_P$1") (pintype "passive"))
    )
    (net (code "64") (name "Net-(J3B-S)") (class "Default")
      (node (ref "J3") (pin "2") (pinfunction "S_2") (pintype "passive"))
      (node (ref "R16") (pin "P$1") (pinfunction "1_P$1") (pintype "passive"))
    )
    (net (code "65") (name "Net-(J3C-S)") (class "Default")
      (node (ref "J3") (pin "3") (pinfunction "S_3") (pintype "passive"))
      (node (ref "R17") (pin "P$1") (pinfunction "1_P$1") (pintype "passive"))
    )
    (net (code "66") (name "Net-(J4B-S)") (class "Default")
      (node (ref "J4") (pin "2") (pinfunction "S_2") (pintype "passive"))
      (node (ref "R18") (pin "P$1") (pinfunction "1_P$1") (pintype "passive"))
    )
    (net (code "67") (name "Net-(J4C-S)") (class "Default")
      (node (ref "J4") (pin "3") (pinfunction "S_3") (pintype "passive"))
      (node (ref "R19") (pin "P$1") (pinfunction "1_P$1") (pintype "passive"))
    )
    (net (code "68") (name "Net-(R3-1)") (class "Default")
      (node (ref "R3") (pin "P$1") (pinfunction "1_P$1") (pintype "passive"))
      (node (ref "SW1") (pin "1") (pinfunction "1_1") (pintype "passive"))
    )
    (net (code "69") (name "Net-(R14-1)") (class "Default")
      (node (ref "P1") (pin "4") (pinfunction "4_4") (pintype "passive"))
      (node (ref "R14") (pin "P$1") (pinfunction "1_P$1") (pintype "passive"))
    )
    (net (code "70") (name "Net-(R15-1)") (class "Default")
      (node (ref "P1") (pin "2") (pinfunction "2_2") (pintype "passive"))
      (node (ref "R15") (pin "P$1") (pinfunction "1_P$1") (pintype "passive"))
    )
    (net (code "71") (name "Net-(R22-1)") (class "Default")
      (node (ref "P1") (pin "36") (pinfunction "36_36") (pintype "passive"))
      (node (ref "R22") (pin "P$1") (pinfunction "1_P$1") (pintype "passive"))
    )
    (net (code "72") (name "Net-(R23-2)") (class "Default")
      (node (ref "P1") (pin "29") (pinfunction "29_29") (pintype "passive"))
      (node (ref "R23") (pin "P$2") (pinfunction "2_P$2") (pintype "passive"))
    )
    (net (code "73") (name "RESETN") (class "Default")
      (node (ref "IC1") (pin "33") (pinfunction "RESET_N_33") (pintype "bidirectional"))
      (node (ref "IC2") (pin "33") (pinfunction "RESET_N_33") (pintype "bidirectional"))
      (node (ref "IC3") (pin "33") (pinfunction "RESET_N_33") (pintype "bidirectional"))
      (node (ref "P2") (pin "26") (pinfunction "26_26") (pintype "passive"))
    )
    (net (code "74") (name "SCL") (class "Default")
      (node (ref "IC1") (pin "1") (pinfunction "SCL_1") (pintype "bidirectional"))
      (node (ref "IC2") (pin "1") (pinfunction "SCL_1") (pintype "bidirectional"))
      (node (ref "IC3") (pin "1") (pinfunction "SCL_1") (pintype "bidirectional"))
      (node (ref "P1") (pin "28") (pinfunction "28_28") (pintype "passive"))
      (node (ref "R24") (pin "P$1") (pinfunction "1_P$1") (pintype "passive"))
    )
    (net (code "75") (name "SDA") (class "Default")
      (node (ref "IC1") (pin "2") (pinfunction "SDA_2") (pintype "bidirectional"))
      (node (ref "IC2") (pin "2") (pinfunction "SDA_2") (pintype "bidirectional"))
      (node (ref "IC3") (pin "2") (pinfunction "SDA_2") (pintype "bidirectional"))
      (node (ref "P1") (pin "26") (pinfunction "26_26") (pintype "passive"))
      (node (ref "R25") (pin "P$1") (pinfunction "1_P$1") (pintype "passive"))
    )
    (net (code "76") (name "SHUTDOWN_REQ{slash}") (class "Default")
      (node (ref "P2") (pin "34") (pinfunction "34_34") (pintype "passive"))
      (node (ref "R3") (pin "P$2") (pinfunction "2_P$2") (pintype "passive"))
    )
    (net (code "77") (name "SPI_ADC_CNV") (class "Default")
      (node (ref "P1") (pin "6") (pinfunction "6_6") (pintype "passive"))
    )
    (net (code "78") (name "SPI_MISO") (class "Default")
      (node (ref "P1") (pin "10") (pinfunction "10_10") (pintype "passive"))
    )
    (net (code "79") (name "SPI_MOSI") (class "Default")
      (node (ref "P1") (pin "12") (pinfunction "12_12") (pintype "passive"))
    )
    (net (code "80") (name "SPI_SCK") (class "Default")
      (node (ref "P1") (pin "8") (pinfunction "8_8") (pintype "passive"))
    )
    (net (code "81") (name "unconnected-(IC1-GPIO1-Pad35)") (class "Default")
      (node (ref "IC1") (pin "35") (pinfunction "GPIO1_35") (pintype "bidirectional"))
    )
    (net (code "82") (name "unconnected-(IC1-GPIO2-Pad34)") (class "Default")
      (node (ref "IC1") (pin "34") (pinfunction "GPIO2_34") (pintype "bidirectional"))
    )
    (net (code "83") (name "unconnected-(IC1-HPLCOM-Pad19)") (class "Default")
      (node (ref "IC1") (pin "19") (pinfunction "HPLCOM_19") (pintype "bidirectional"))
    )
    (net (code "84") (name "unconnected-(IC1-HPRCOM-Pad22)") (class "Default")
      (node (ref "IC1") (pin "22") (pinfunction "HPRCOM_22") (pintype "bidirectional"))
    )
    (net (code "85") (name "unconnected-(IC1-LINE1LM-Pad4)") (class "Default")
      (node (ref "IC1") (pin "4") (pinfunction "LINE1LM_4") (pintype "bidirectional"))
    )
    (net (code "86") (name "unconnected-(IC1-LINE1LP-Pad3)") (class "Default")
      (node (ref "IC1") (pin "3") (pinfunction "LINE1LP_3") (pintype "bidirectional"))
    )
    (net (code "87") (name "unconnected-(IC1-LINE1RM-Pad6)") (class "Default")
      (node (ref "IC1") (pin "6") (pinfunction "LINE1RM_6") (pintype "bidirectional"))
    )
    (net (code "88") (name "unconnected-(IC1-LINE1RP-Pad5)") (class "Default")
      (node (ref "IC1") (pin "5") (pinfunction "LINE1RP_5") (pintype "bidirectional"))
    )
    (net (code "89") (name "unconnected-(IC1-MFP2-Pad47)") (class "Default")
      (node (ref "IC1") (pin "47") (pinfunction "MFP2_47") (pintype "bidirectional"))
    )
    (net (code "90") (name "unconnected-(IC1-MFP3-Pad48)") (class "Default")
      (node (ref "IC1") (pin "48") (pinfunction "MFP3_48") (pintype "bidirectional"))
    )
    (net (code "91") (name "unconnected-(IC1-MIC3L-Pad11)") (class "Default")
      (node (ref "IC1") (pin "11") (pinfunction "MIC3L_11") (pintype "bidirectional"))
    )
    (net (code "92") (name "unconnected-(IC1-MIC3R-Pad14)") (class "Default")
      (node (ref "IC1") (pin "14") (pinfunction "MIC3R_14") (pintype "bidirectional"))
    )
    (net (code "93") (name "unconnected-(IC1-MICBIAS-Pad13)") (class "Default")
      (node (ref "IC1") (pin "13") (pinfunction "MICBIAS_13") (pintype "bidirectional"))
    )
    (net (code "94") (name "unconnected-(IC1-MICDET-Pad12)") (class "Default")
      (node (ref "IC1") (pin "12") (pinfunction "MICDET_12") (pintype "bidirectional"))
    )
    (net (code "95") (name "unconnected-(IC1-MONO_LOM-Pad28)") (class "Default")
      (node (ref "IC1") (pin "28") (pinfunction "MONO_LOM_28") (pintype "bidirectional"))
    )
    (net (code "96") (name "unconnected-(IC1-MONO_LOP-Pad27)") (class "Default")
      (node (ref "IC1") (pin "27") (pinfunction "MONO_LOP_27") (pintype "bidirectional"))
    )
    (net (code "97") (name "unconnected-(IC2-GPIO1-Pad35)") (class "Default")
      (node (ref "IC2") (pin "35") (pinfunction "GPIO1_35") (pintype "bidirectional"))
    )
    (net (code "98") (name "unconnected-(IC2-GPIO2-Pad34)") (class "Default")
      (node (ref "IC2") (pin "34") (pinfunction "GPIO2_34") (pintype "bidirectional"))
    )
    (net (code "99") (name "unconnected-(IC2-HPLCOM-Pad19)") (class "Default")
      (node (ref "IC2") (pin "19") (pinfunction "HPLCOM_19") (pintype "bidirectional"))
    )
    (net (code "100") (name "unconnected-(IC2-HPRCOM-Pad22)") (class "Default")
      (node (ref "IC2") (pin "22") (pinfunction "HPRCOM_22") (pintype "bidirectional"))
    )
    (net (code "101") (name "unconnected-(IC2-LINE1LM-Pad4)") (class "Default")
      (node (ref "IC2") (pin "4") (pinfunction "LINE1LM_4") (pintype "bidirectional"))
    )
    (net (code "102") (name "unconnected-(IC2-LINE1LP-Pad3)") (class "Default")
      (node (ref "IC2") (pin "3") (pinfunction "LINE1LP_3") (pintype "bidirectional"))
    )
    (net (code "103") (name "unconnected-(IC2-LINE1RM-Pad6)") (class "Default")
      (node (ref "IC2") (pin "6") (pinfunction "LINE1RM_6") (pintype "bidirectional"))
    )
    (net (code "104") (name "unconnected-(IC2-LINE1RP-Pad5)") (class "Default")
      (node (ref "IC2") (pin "5") (pinfunction "LINE1RP_5") (pintype "bidirectional"))
    )
    (net (code "105") (name "unconnected-(IC2-MFP2-Pad47)") (class "Default")
      (node (ref "IC2") (pin "47") (pinfunction "MFP2_47") (pintype "bidirectional"))
    )
    (net (code "106") (name "unconnected-(IC2-MFP3-Pad48)") (class "Default")
      (node (ref "IC2") (pin "48") (pinfunction "MFP3_48") (pintype "bidirectional"))
    )
    (net (code "107") (name "unconnected-(IC2-MIC3L-Pad11)") (class "Default")
      (node (ref "IC2") (pin "11") (pinfunction "MIC3L_11") (pintype "bidirectional"))
    )
    (net (code "108") (name "unconnected-(IC2-MIC3R-Pad14)") (class "Default")
      (node (ref "IC2") (pin "14") (pinfunction "MIC3R_14") (pintype "bidirectional"))
    )
    (net (code "109") (name "unconnected-(IC2-MICDET-Pad12)") (class "Default")
      (node (ref "IC2") (pin "12") (pinfunction "MICDET_12") (pintype "bidirectional"))
    )
    (net (code "110") (name "unconnected-(IC2-MONO_LOM-Pad28)") (class "Default")
      (node (ref "IC2") (pin "28") (pinfunction "MONO_LOM_28") (pintype "bidirectional"))
    )
    (net (code "111") (name "unconnected-(IC2-MONO_LOP-Pad27)") (class "Default")
      (node (ref "IC2") (pin "27") (pinfunction "MONO_LOP_27") (pintype "bidirectional"))
    )
    (net (code "112") (name "unconnected-(IC3-GPIO1-Pad35)") (class "Default")
      (node (ref "IC3") (pin "35") (pinfunction "GPIO1_35") (pintype "bidirectional"))
    )
    (net (code "113") (name "unconnected-(IC3-GPIO2-Pad34)") (class "Default")
      (node (ref "IC3") (pin "34") (pinfunction "GPIO2_34") (pintype "bidirectional"))
    )
    (net (code "114") (name "unconnected-(IC3-HPLCOM-Pad19)") (class "Default")
      (node (ref "IC3") (pin "19") (pinfunction "HPLCOM_19") (pintype "bidirectional"))
    )
    (net (code "115") (name "unconnected-(IC3-HPRCOM-Pad22)") (class "Default")
      (node (ref "IC3") (pin "22") (pinfunction "HPRCOM_22") (pintype "bidirectional"))
    )
    (net (code "116") (name "unconnected-(IC3-LINE1LM-Pad4)") (class "Default")
      (node (ref "IC3") (pin "4") (pinfunction "LINE1LM_4") (pintype "bidirectional"))
    )
    (net (code "117") (name "unconnected-(IC3-LINE1LP-Pad3)") (class "Default")
      (node (ref "IC3") (pin "3") (pinfunction "LINE1LP_3") (pintype "bidirectional"))
    )
    (net (code "118") (name "unconnected-(IC3-LINE1RM-Pad6)") (class "Default")
      (node (ref "IC3") (pin "6") (pinfunction "LINE1RM_6") (pintype "bidirectional"))
    )
    (net (code "119") (name "unconnected-(IC3-LINE1RP-Pad5)") (class "Default")
      (node (ref "IC3") (pin "5") (pinfunction "LINE1RP_5") (pintype "bidirectional"))
    )
    (net (code "120") (name "unconnected-(IC3-MFP2-Pad47)") (class "Default")
      (node (ref "IC3") (pin "47") (pinfunction "MFP2_47") (pintype "bidirectional"))
    )
    (net (code "121") (name "unconnected-(IC3-MFP3-Pad48)") (class "Default")
      (node (ref "IC3") (pin "48") (pinfunction "MFP3_48") (pintype "bidirectional"))
    )
    (net (code "122") (name "unconnected-(IC3-MIC3L-Pad11)") (class "Default")
      (node (ref "IC3") (pin "11") (pinfunction "MIC3L_11") (pintype "bidirectional"))
    )
    (net (code "123") (name "unconnected-(IC3-MIC3R-Pad14)") (class "Default")
      (node (ref "IC3") (pin "14") (pinfunction "MIC3R_14") (pintype "bidirectional"))
    )
    (net (code "124") (name "unconnected-(IC3-MICBIAS-Pad13)") (class "Default")
      (node (ref "IC3") (pin "13") (pinfunction "MICBIAS_13") (pintype "bidirectional"))
    )
    (net (code "125") (name "unconnected-(IC3-MICDET-Pad12)") (class "Default")
      (node (ref "IC3") (pin "12") (pinfunction "MICDET_12") (pintype "bidirectional"))
    )
    (net (code "126") (name "unconnected-(IC3-MONO_LOM-Pad28)") (class "Default")
      (node (ref "IC3") (pin "28") (pinfunction "MONO_LOM_28") (pintype "bidirectional"))
    )
    (net (code "127") (name "unconnected-(IC3-MONO_LOP-Pad27)") (class "Default")
      (node (ref "IC3") (pin "27") (pinfunction "MONO_LOP_27") (pintype "bidirectional"))
    )
    (net (code "128") (name "unconnected-(IC4-BP-Pad4)") (class "Default")
      (node (ref "IC4") (pin "4") (pinfunction "BP_4") (pintype "input"))
    )
    (net (code "129") (name "unconnected-(P1-Pad1)") (class "Default")
      (node (ref "P1") (pin "1") (pinfunction "1_1") (pintype "passive"))
    )
    (net (code "130") (name "unconnected-(P1-Pad3)") (class "Default")
      (node (ref "P1") (pin "3") (pinfunction "3_3") (pintype "passive"))
    )
    (net (code "131") (name "unconnected-(P1-Pad5)") (class "Default")
      (node (ref "P1") (pin "5") (pinfunction "5_5") (pintype "passive"))
    )
    (net (code "132") (name "unconnected-(P1-Pad7)") (class "Default")
      (node (ref "P1") (pin "7") (pinfunction "7_7") (pintype "passive"))
    )
    (net (code "133") (name "unconnected-(P1-Pad9)") (class "Default")
      (node (ref "P1") (pin "9") (pinfunction "9_9") (pintype "passive"))
    )
    (net (code "134") (name "unconnected-(P1-Pad11)") (class "Default")
      (node (ref "P1") (pin "11") (pinfunction "11_11") (pintype "passive"))
    )
    (net (code "135") (name "unconnected-(P1-Pad13)") (class "Default")
      (node (ref "P1") (pin "13") (pinfunction "13_13") (pintype "passive"))
    )
    (net (code "136") (name "unconnected-(P1-Pad15)") (class "Default")
      (node (ref "P1") (pin "15") (pinfunction "15_15") (pintype "passive"))
    )
    (net (code "137") (name "unconnected-(P1-Pad17)") (class "Default")
      (node (ref "P1") (pin "17") (pinfunction "17_17") (pintype "passive"))
    )
    (net (code "138") (name "unconnected-(P1-Pad18)") (class "Default")
      (node (ref "P1") (pin "18") (pinfunction "18_18") (pintype "passive"))
    )
    (net (code "139") (name "unconnected-(P1-Pad19)") (class "Default")
      (node (ref "P1") (pin "19") (pinfunction "19_19") (pintype "passive"))
    )
    (net (code "140") (name "unconnected-(P1-Pad20)") (class "Default")
      (node (ref "P1") (pin "20") (pinfunction "20_20") (pintype "passive"))
    )
    (net (code "141") (name "unconnected-(P1-Pad21)") (class "Default")
      (node (ref "P1") (pin "21") (pinfunction "21_21") (pintype "passive"))
    )
    (net (code "142") (name "unconnected-(P1-Pad23)") (class "Default")
      (node (ref "P1") (pin "23") (pinfunction "23_23") (pintype "passive"))
    )
    (net (code "143") (name "unconnected-(P1-Pad25)") (class "Default")
      (node (ref "P1") (pin "25") (pinfunction "25_25") (pintype "passive"))
    )
    (net (code "144") (name "unconnected-(P1-Pad27)") (class "Default")
      (node (ref "P1") (pin "27") (pinfunction "27_27") (pintype "passive"))
    )
    (net (code "145") (name "unconnected-(P1-Pad30)") (class "Default")
      (node (ref "P1") (pin "30") (pinfunction "30_30") (pintype "passive"))
    )
    (net (code "146") (name "unconnected-(P1-Pad31)") (class "Default")
      (node (ref "P1") (pin "31") (pinfunction "31_31") (pintype "passive"))
    )
    (net (code "147") (name "unconnected-(P1-Pad32)") (class "Default")
      (node (ref "P1") (pin "32") (pinfunction "32_32") (pintype "passive"))
    )
    (net (code "148") (name "unconnected-(P1-Pad34)") (class "Default")
      (node (ref "P1") (pin "34") (pinfunction "34_34") (pintype "passive"))
    )
    (net (code "149") (name "unconnected-(P1-Pad35)") (class "Default")
      (node (ref "P1") (pin "35") (pinfunction "35_35") (pintype "passive"))
    )
    (net (code "150") (name "unconnected-(P2-Pad1)") (class "Default")
      (node (ref "P2") (pin "1") (pinfunction "1_1") (pintype "passive"))
    )
    (net (code "151") (name "unconnected-(P2-Pad2)") (class "Default")
      (node (ref "P2") (pin "2") (pinfunction "2_2") (pintype "passive"))
    )
    (net (code "152") (name "unconnected-(P2-Pad3)") (class "Default")
      (node (ref "P2") (pin "3") (pinfunction "3_3") (pintype "passive"))
    )
    (net (code "153") (name "unconnected-(P2-Pad4)") (class "Default")
      (node (ref "P2") (pin "4") (pinfunction "4_4") (pintype "passive"))
    )
    (net (code "154") (name "unconnected-(P2-Pad5)") (class "Default")
      (node (ref "P2") (pin "5") (pinfunction "5_5") (pintype "passive"))
    )
    (net (code "155") (name "unconnected-(P2-Pad6)") (class "Default")
      (node (ref "P2") (pin "6") (pinfunction "6_6") (pintype "passive"))
    )
    (net (code "156") (name "unconnected-(P2-Pad7)") (class "Default")
      (node (ref "P2") (pin "7") (pinfunction "7_7") (pintype "passive"))
    )
    (net (code "157") (name "unconnected-(P2-Pad8)") (class "Default")
      (node (ref "P2") (pin "8") (pinfunction "8_8") (pintype "passive"))
    )
    (net (code "158") (name "unconnected-(P2-Pad9)") (class "Default")
      (node (ref "P2") (pin "9") (pinfunction "9_9") (pintype "passive"))
    )
    (net (code "159") (name "unconnected-(P2-Pad10)") (class "Default")
      (node (ref "P2") (pin "10") (pinfunction "10_10") (pintype "passive"))
    )
    (net (code "160") (name "unconnected-(P2-Pad11)") (class "Default")
      (node (ref "P2") (pin "11") (pinfunction "11_11") (pintype "passive"))
    )
    (net (code "161") (name "unconnected-(P2-Pad12)") (class "Default")
      (node (ref "P2") (pin "12") (pinfunction "12_12") (pintype "passive"))
    )
    (net (code "162") (name "unconnected-(P2-Pad13)") (class "Default")
      (node (ref "P2") (pin "13") (pinfunction "13_13") (pintype "passive"))
    )
    (net (code "163") (name "unconnected-(P2-Pad14)") (class "Default")
      (node (ref "P2") (pin "14") (pinfunction "14_14") (pintype "passive"))
    )
    (net (code "164") (name "unconnected-(P2-Pad16)") (class "Default")
      (node (ref "P2") (pin "16") (pinfunction "16_16") (pintype "passive"))
    )
    (net (code "165") (name "unconnected-(P2-Pad17)") (class "Default")
      (node (ref "P2") (pin "17") (pinfunction "17_17") (pintype "passive"))
    )
    (net (code "166") (name "unconnected-(P2-Pad18)") (class "Default")
      (node (ref "P2") (pin "18") (pinfunction "18_18") (pintype "passive"))
    )
    (net (code "167") (name "unconnected-(P2-Pad19)") (class "Default")
      (node (ref "P2") (pin "19") (pinfunction "19_19") (pintype "passive"))
    )
    (net (code "168") (name "unconnected-(P2-Pad20)") (class "Default")
      (node (ref "P2") (pin "20") (pinfunction "20_20") (pintype "passive"))
    )
    (net (code "169") (name "unconnected-(P2-Pad22)") (class "Default")
      (node (ref "P2") (pin "22") (pinfunction "22_22") (pintype "passive"))
    )
    (net (code "170") (name "unconnected-(P2-Pad23)") (class "Default")
      (node (ref "P2") (pin "23") (pinfunction "23_23") (pintype "passive"))
    )
    (net (code "171") (name "unconnected-(P2-Pad24)") (class "Default")
      (node (ref "P2") (pin "24") (pinfunction "24_24") (pintype "passive"))
    )
    (net (code "172") (name "unconnected-(P2-Pad25)") (class "Default")
      (node (ref "P2") (pin "25") (pinfunction "25_25") (pintype "passive"))
    )
    (net (code "173") (name "unconnected-(P2-Pad27)") (class "Default")
      (node (ref "P2") (pin "27") (pinfunction "27_27") (pintype "passive"))
    )
    (net (code "174") (name "unconnected-(P2-Pad28)") (class "Default")
      (node (ref "P2") (pin "28") (pinfunction "28_28") (pintype "passive"))
    )
    (net (code "175") (name "unconnected-(P2-Pad29)") (class "Default")
      (node (ref "P2") (pin "29") (pinfunction "29_29") (pintype "passive"))
    )
    (net (code "176") (name "unconnected-(P2-Pad31)") (class "Default")
      (node (ref "P2") (pin "31") (pinfunction "31_31") (pintype "passive"))
    )
    (net (code "177") (name "unconnected-(P2-Pad33)") (class "Default")
      (node (ref "P2") (pin "33") (pinfunction "33_33") (pintype "passive"))
    )
    (net (code "178") (name "unconnected-(P2-Pad35)") (class "Default")
      (node (ref "P2") (pin "35") (pinfunction "35_35") (pintype "passive"))
    )
    (net (code "179") (name "unconnected-(P2-Pad36)") (class "Default")
      (node (ref "P2") (pin "36") (pinfunction "36_36") (pintype "passive"))
    )
  )
)
